# 6_-H3_MAIN.net
KiCad netlist of a schematic drawn in Altium Designer
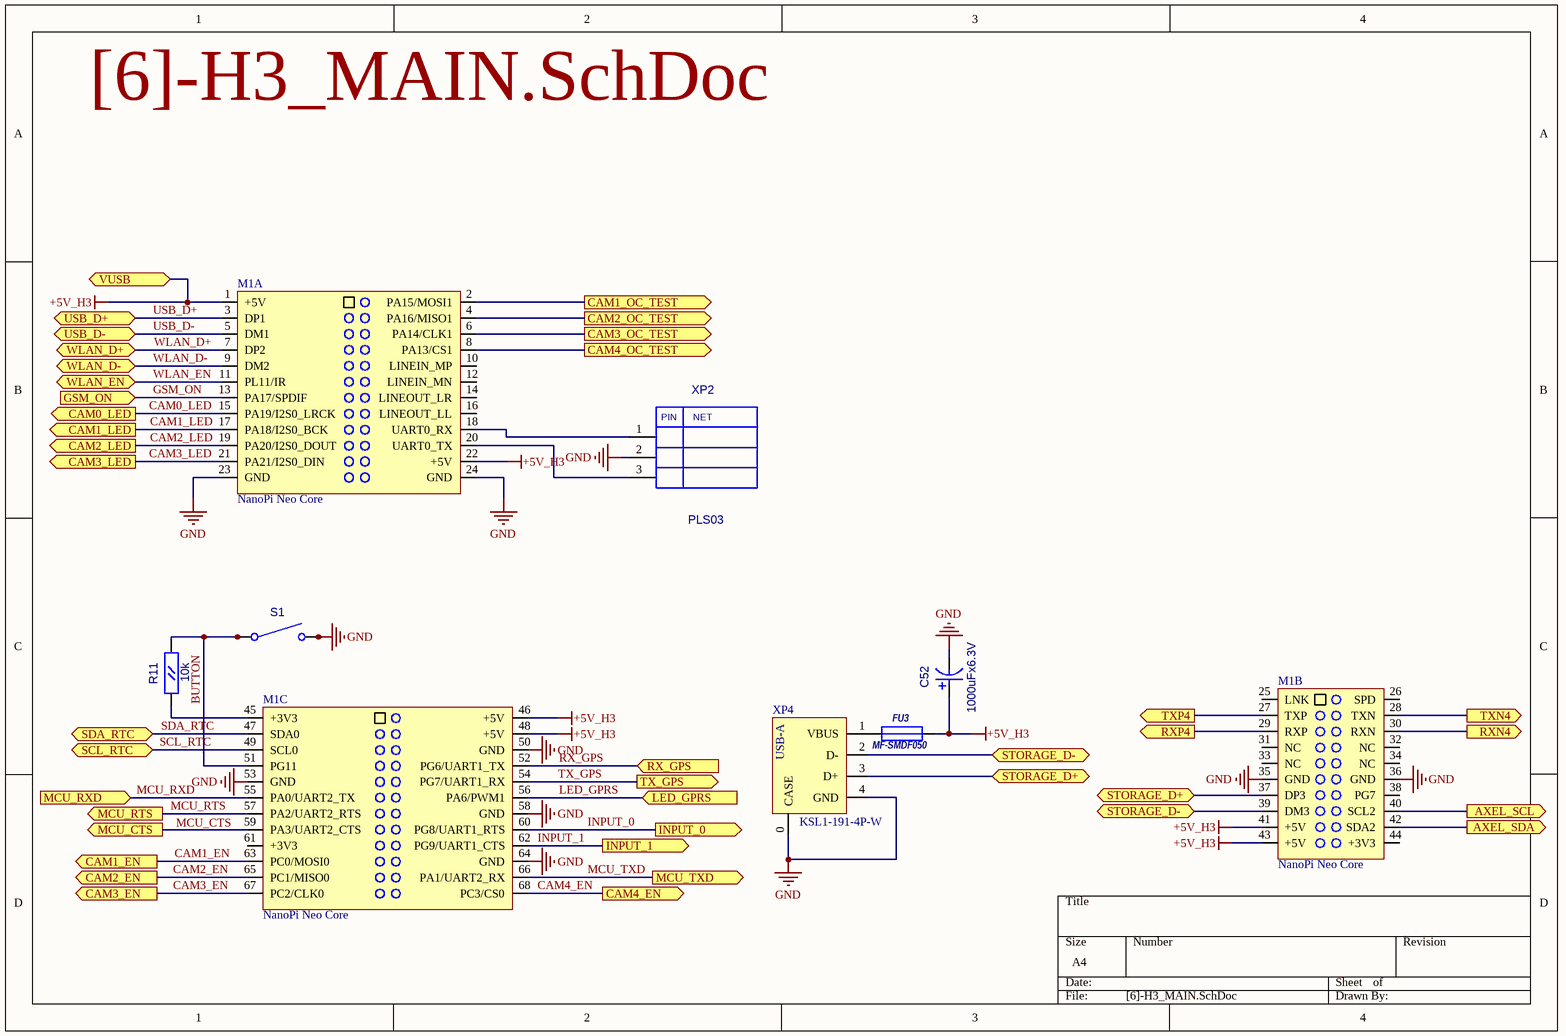
[diagram p0: [6]-H3_MAIN.SchDoc]

(export (version "E")
  (design (tool "Eeschema 10.0.6"))
  (components
    (comp (ref "C52")
      (value "1000uFx6.3V")
      (footprint "CC8X3.5")
      (description "CAP0.35")
      (libsource (lib "gprs_modem_2") (part "CAP0.35"))
    )
    (comp (ref "FU3")
      (value "MF-SMDF050")
      (footprint "MF-SMDF")
      (description "MF-SMDF")
      (libsource (lib "fizik_lib") (part "MF-SMDF"))
    )
    (comp (ref "M1")
      (value "NanoPi Neo Core")
      (footprint "NanoPiNeo_CORE")
      (description "Nano Pi Neo Core Allwinner H3 based embedded module")
      (libsource (lib "") (part "NanoPi Neo Core_1"))
    )
    (comp (ref "R11")
      (value "10k")
      (footprint "RC0603")
      (description "RC0603")
      (libsource (lib "fizik_lib") (part "RC0603"))
    )
    (comp (ref "S1")
      (value "DTSM-61N")
      (footprint "DTSM-61N")
      (description "Switch, Single Pole, Single Throw, Normally Open")
      (libsource (lib "fizik_lib") (part "DTSM-61N"))
    )
    (comp (ref "XP2") (value "PLS03") (footprint "PLS-03") (libsource (lib "fizik_lib") (part "PLS03")))
    (comp (ref "XP4")
      (value "KSL1-191-4P-W")
      (footprint "USB_A_REAR")
      (description "USB A rear side connector")
      (libsource (lib "fizik_lib") (part "USB_A_REAR"))
    )
  )
  (nets
    (net (code "1") (name "+5V_H3") (class "Default")
      (node (ref "C52") (pin "1") (pintype "passive"))
      (node (ref "FU3") (pin "2") (pintype "passive"))
      (node (ref "M1") (pin "1") (pinfunction "+5V_1") (pintype "passive"))
      (node (ref "M1") (pin "22") (pinfunction "+5V_22") (pintype "passive"))
      (node (ref "M1") (pin "41") (pinfunction "+5V_41") (pintype "passive"))
      (node (ref "M1") (pin "43") (pinfunction "+5V_43") (pintype "passive"))
      (node (ref "M1") (pin "46") (pinfunction "+5V_46") (pintype "passive"))
      (node (ref "M1") (pin "48") (pinfunction "+5V_48") (pintype "passive"))
    )
    (net (code "2") (name "/AXEL_SCL") (class "Default")
      (node (ref "M1") (pin "40") (pinfunction "SCL2_40") (pintype "passive"))
    )
    (net (code "3") (name "/AXEL_SDA") (class "Default")
      (node (ref "M1") (pin "42") (pinfunction "SDA2_42") (pintype "passive"))
    )
    (net (code "4") (name "/BUTTON") (class "Default")
      (node (ref "M1") (pin "51") (pinfunction "PG11_51") (pintype "passive"))
      (node (ref "R11") (pin "2") (pinfunction "B_2") (pintype "passive"))
      (node (ref "S1") (pin "1") (pinfunction "C1_1") (pintype "passive"))
      (node (ref "S1") (pin "2") (pintype "passive"))
    )
    (net (code "5") (name "/CAM0_LED") (class "Default")
      (node (ref "M1") (pin "15") (pinfunction "PA19/I2S0_LRCK_15") (pintype "passive"))
    )
    (net (code "6") (name "/CAM1_EN") (class "Default")
      (node (ref "M1") (pin "63") (pinfunction "PC0/MOSI0_63") (pintype "passive"))
    )
    (net (code "7") (name "/CAM1_LED") (class "Default")
      (node (ref "M1") (pin "17") (pinfunction "PA18/I2S0_BCK_17") (pintype "passive"))
    )
    (net (code "8") (name "/CAM1_OC_TEST") (class "Default")
      (node (ref "M1") (pin "2") (pinfunction "PA15/MOSI1_2") (pintype "passive"))
    )
    (net (code "9") (name "/CAM2_EN") (class "Default")
      (node (ref "M1") (pin "65") (pinfunction "PC1/MISO0_65") (pintype "passive"))
    )
    (net (code "10") (name "/CAM2_LED") (class "Default")
      (node (ref "M1") (pin "19") (pinfunction "PA20/I2S0_DOUT_19") (pintype "passive"))
    )
    (net (code "11") (name "/CAM2_OC_TEST") (class "Default")
      (node (ref "M1") (pin "4") (pinfunction "PA16/MISO1_4") (pintype "passive"))
    )
    (net (code "12") (name "/CAM3_EN") (class "Default")
      (node (ref "M1") (pin "67") (pinfunction "PC2/CLK0_67") (pintype "passive"))
    )
    (net (code "13") (name "/CAM3_LED") (class "Default")
      (node (ref "M1") (pin "21") (pinfunction "PA21/I2S0_DIN_21") (pintype "passive"))
    )
    (net (code "14") (name "/CAM3_OC_TEST") (class "Default")
      (node (ref "M1") (pin "6") (pinfunction "PA14/CLK1_6") (pintype "passive"))
    )
    (net (code "15") (name "/CAM4_EN") (class "Default")
      (node (ref "M1") (pin "68") (pinfunction "PC3/CS0_68") (pintype "passive"))
    )
    (net (code "16") (name "/CAM4_OC_TEST") (class "Default")
      (node (ref "M1") (pin "8") (pinfunction "PA13/CS1_8") (pintype "passive"))
    )
    (net (code "17") (name "/GSM_ON") (class "Default")
      (node (ref "M1") (pin "13") (pinfunction "PA17/SPDIF_13") (pintype "passive"))
    )
    (net (code "18") (name "/INPUT_0") (class "Default")
      (node (ref "M1") (pin "60") (pinfunction "PG8/UART1_RTS_60") (pintype "passive"))
    )
    (net (code "19") (name "/INPUT_1") (class "Default")
      (node (ref "M1") (pin "62") (pinfunction "PG9/UART1_CTS_62") (pintype "passive"))
    )
    (net (code "20") (name "/LED_GPRS") (class "Default")
      (node (ref "M1") (pin "56") (pinfunction "PA6/PWM1_56") (pintype "passive"))
    )
    (net (code "21") (name "/MCU_CTS") (class "Default")
      (node (ref "M1") (pin "59") (pinfunction "PA3/UART2_CTS_59") (pintype "passive"))
    )
    (net (code "22") (name "/MCU_RTS") (class "Default")
      (node (ref "M1") (pin "57") (pinfunction "PA2/UART2_RTS_57") (pintype "passive"))
    )
    (net (code "23") (name "/MCU_RXD") (class "Default")
      (node (ref "M1") (pin "55") (pinfunction "PA0/UART2_TX_55") (pintype "passive"))
    )
    (net (code "24") (name "/MCU_TXD") (class "Default")
      (node (ref "M1") (pin "66") (pinfunction "PA1/UART2_RX_66") (pintype "passive"))
    )
    (net (code "25") (name "/RXN4") (class "Default")
      (node (ref "M1") (pin "30") (pinfunction "RXN_30") (pintype "passive"))
    )
    (net (code "26") (name "/RXP4") (class "Default")
      (node (ref "M1") (pin "29") (pinfunction "RXP_29") (pintype "passive"))
    )
    (net (code "27") (name "/RX_GPS") (class "Default")
      (node (ref "M1") (pin "52") (pinfunction "PG6/UART1_TX_52") (pintype "passive"))
    )
    (net (code "28") (name "/SCL_RTC") (class "Default")
      (node (ref "M1") (pin "49") (pinfunction "SCL0_49") (pintype "passive"))
    )
    (net (code "29") (name "/SDA_RTC") (class "Default")
      (node (ref "M1") (pin "47") (pinfunction "SDA0_47") (pintype "passive"))
    )
    (net (code "30") (name "/STORAGE_D+") (class "Default")
      (node (ref "M1") (pin "37") (pinfunction "DP3_37") (pintype "passive"))
      (node (ref "XP4") (pin "3") (pinfunction "D+_3") (pintype "passive"))
    )
    (net (code "31") (name "/STORAGE_D-") (class "Default")
      (node (ref "M1") (pin "39") (pinfunction "DM3_39") (pintype "passive"))
      (node (ref "XP4") (pin "2") (pinfunction "D-_2") (pintype "passive"))
    )
    (net (code "32") (name "/TXN4") (class "Default")
      (node (ref "M1") (pin "28") (pinfunction "TXN_28") (pintype "passive"))
    )
    (net (code "33") (name "/TXP4") (class "Default")
      (node (ref "M1") (pin "27") (pinfunction "TXP_27") (pintype "passive"))
    )
    (net (code "34") (name "/TX_GPS") (class "Default")
      (node (ref "M1") (pin "54") (pinfunction "PG7/UART1_RX_54") (pintype "passive"))
    )
    (net (code "35") (name "/USB_D+") (class "Default")
      (node (ref "M1") (pin "3") (pinfunction "DP1_3") (pintype "passive"))
    )
    (net (code "36") (name "/USB_D-") (class "Default")
      (node (ref "M1") (pin "5") (pinfunction "DM1_5") (pintype "passive"))
    )
    (net (code "37") (name "/WLAN_D+") (class "Default")
      (node (ref "M1") (pin "7") (pinfunction "DP2_7") (pintype "passive"))
    )
    (net (code "38") (name "/WLAN_D-") (class "Default")
      (node (ref "M1") (pin "9") (pinfunction "DM2_9") (pintype "passive"))
    )
    (net (code "39") (name "/WLAN_EN") (class "Default")
      (node (ref "M1") (pin "11") (pinfunction "PL11/IR_11") (pintype "passive"))
    )
    (net (code "40") (name "GND") (class "Default")
      (node (ref "C52") (pin "2") (pintype "passive"))
      (node (ref "M1") (pin "23") (pinfunction "GND_23") (pintype "passive"))
      (node (ref "M1") (pin "24") (pinfunction "GND_24") (pintype "passive"))
      (node (ref "M1") (pin "35") (pinfunction "GND_35") (pintype "passive"))
      (node (ref "M1") (pin "36") (pinfunction "GND_36") (pintype "passive"))
      (node (ref "M1") (pin "50") (pinfunction "GND_50") (pintype "passive"))
      (node (ref "M1") (pin "53") (pinfunction "GND_53") (pintype "passive"))
      (node (ref "M1") (pin "58") (pinfunction "GND_58") (pintype "passive"))
      (node (ref "M1") (pin "64") (pinfunction "GND_64") (pintype "passive"))
      (node (ref "S1") (pin "3") (pinfunction "C2_3") (pintype "passive"))
      (node (ref "S1") (pin "4") (pintype "passive"))
      (node (ref "XP2") (pin "2") (pinfunction "2_2") (pintype "passive"))
      (node (ref "XP4") (pin "0") (pinfunction "CASE_0") (pintype "passive"))
      (node (ref "XP4") (pin "4") (pinfunction "GND_4") (pintype "passive"))
    )
    (net (code "41") (name "Net-(M1A-UART0_RX)") (class "Default")
      (node (ref "M1") (pin "18") (pinfunction "UART0_RX_18") (pintype "passive"))
      (node (ref "XP2") (pin "1") (pinfunction "1_1") (pintype "passive"))
    )
    (net (code "42") (name "Net-(M1A-UART0_TX)") (class "Default")
      (node (ref "M1") (pin "20") (pinfunction "UART0_TX_20") (pintype "passive"))
      (node (ref "XP2") (pin "3") (pinfunction "3_3") (pintype "passive"))
    )
    (net (code "43") (name "Net-(R11-A)") (class "Default")
      (node (ref "M1") (pin "45") (pinfunction "+3V3_45") (pintype "passive"))
      (node (ref "R11") (pin "1") (pinfunction "A_1") (pintype "passive"))
    )
    (net (code "44") (name "Net-(XP4-VBUS)") (class "Default")
      (node (ref "FU3") (pin "1") (pintype "passive"))
      (node (ref "XP4") (pin "1") (pinfunction "VBUS_1") (pintype "passive"))
    )
    (net (code "45") (name "unconnected-(M1A-LINEIN_MN-Pad12)") (class "Default")
      (node (ref "M1") (pin "12") (pinfunction "LINEIN_MN_12") (pintype "passive"))
    )
    (net (code "46") (name "unconnected-(M1A-LINEIN_MP-Pad10)") (class "Default")
      (node (ref "M1") (pin "10") (pinfunction "LINEIN_MP_10") (pintype "passive"))
    )
    (net (code "47") (name "unconnected-(M1A-LINEOUT_LL-Pad16)") (class "Default")
      (node (ref "M1") (pin "16") (pinfunction "LINEOUT_LL_16") (pintype "passive"))
    )
    (net (code "48") (name "unconnected-(M1A-LINEOUT_LR-Pad14)") (class "Default")
      (node (ref "M1") (pin "14") (pinfunction "LINEOUT_LR_14") (pintype "passive"))
    )
    (net (code "49") (name "unconnected-(M1B-+3V3-Pad44)") (class "Default")
      (node (ref "M1") (pin "44") (pinfunction "+3V3_44") (pintype "passive"))
    )
    (net (code "50") (name "unconnected-(M1B-LNK-Pad25)") (class "Default")
      (node (ref "M1") (pin "25") (pinfunction "LNK_25") (pintype "passive"))
    )
    (net (code "51") (name "unconnected-(M1B-NC-Pad31)") (class "Default")
      (node (ref "M1") (pin "31") (pinfunction "NC_31") (pintype "passive"))
    )
    (net (code "52") (name "unconnected-(M1B-NC-Pad32)") (class "Default")
      (node (ref "M1") (pin "32") (pinfunction "NC_32") (pintype "passive"))
    )
    (net (code "53") (name "unconnected-(M1B-NC-Pad33)") (class "Default")
      (node (ref "M1") (pin "33") (pinfunction "NC_33") (pintype "passive"))
    )
    (net (code "54") (name "unconnected-(M1B-NC-Pad34)") (class "Default")
      (node (ref "M1") (pin "34") (pinfunction "NC_34") (pintype "passive"))
    )
    (net (code "55") (name "unconnected-(M1B-PG7-Pad38)") (class "Default")
      (node (ref "M1") (pin "38") (pinfunction "PG7_38") (pintype "passive"))
    )
    (net (code "56") (name "unconnected-(M1B-SPD-Pad26)") (class "Default")
      (node (ref "M1") (pin "26") (pinfunction "SPD_26") (pintype "passive"))
    )
    (net (code "57") (name "unconnected-(M1C-+3V3-Pad61)") (class "Default")
      (node (ref "M1") (pin "61") (pinfunction "+3V3_61") (pintype "passive"))
    )
  )
)
